# mems.net
KiCad netlist of a schematic drawn in Altium Designer
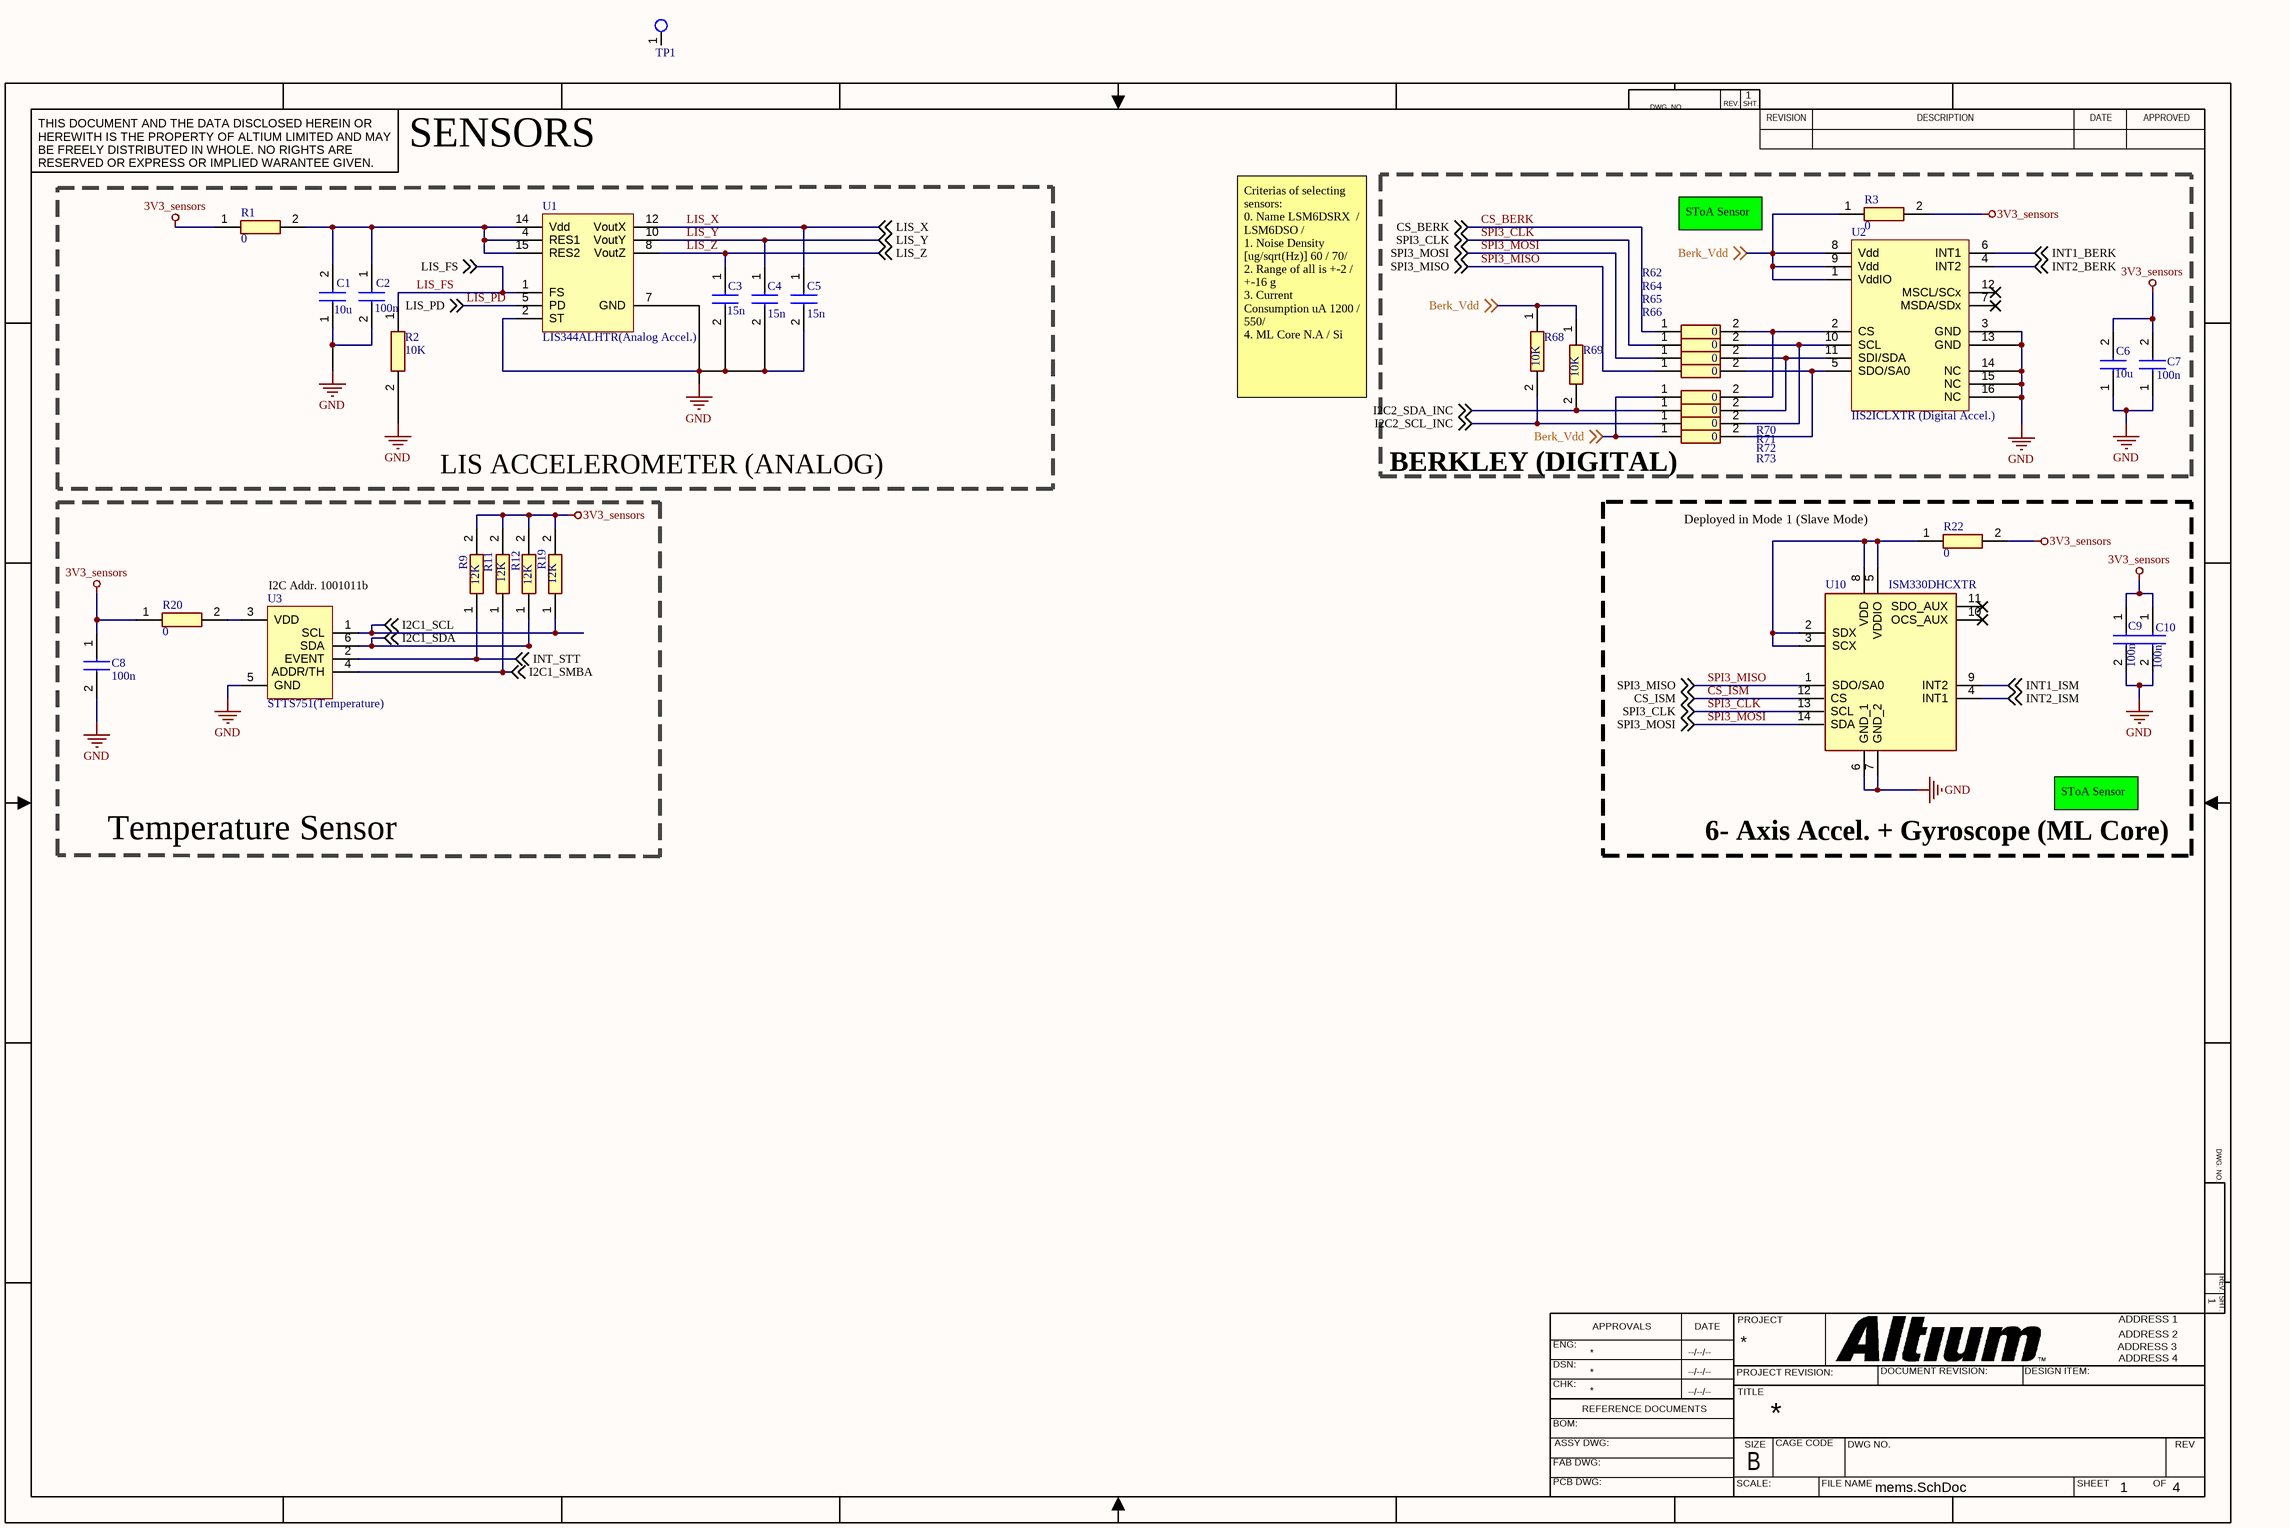
[diagram p0: mems.SchDoc]

(export (version "E")
  (design (tool "Eeschema 10.0.6"))
  (components
    (comp (ref "C1")
      (value "10u")
      (footprint "SamacSys:CAPC1608X100N")
      (description "Capacitor")
      (fields
        (field (name "MOUSER2 PART NUMBER") "963-LMK107BBJ106KALT")
        (field (name "MANUFACTURER_PART_NUMBER") "LMK107BBJ106KALT")
      )
      (libsource (lib "*") (part "LMK107BBJ106KALT"))
    )
    (comp (ref "C2")
      (value "100n")
      (footprint "SamacSys:CAPC1608X87N")
      (description "Capacitor")
      (fields (field (name "MANUFACTURER_PART_NUMBER") "885012206071"))
      (libsource (lib "*") (part "885012206071"))
    )
    (comp (ref "C3")
      (value "15n")
      (footprint "SamacSys:CAPC1608X87N")
      (description "Capacitor")
      (fields (field (name "MANUFACTURER_PART_NUMBER") "885012206041"))
      (libsource (lib "*") (part "885012206041"))
    )
    (comp (ref "C4")
      (value "15n")
      (footprint "SamacSys:CAPC1608X87N")
      (description "Capacitor")
      (fields (field (name "MANUFACTURER_PART_NUMBER") "885012206041"))
      (libsource (lib "*") (part "885012206041"))
    )
    (comp (ref "C5")
      (value "15n")
      (footprint "SamacSys:CAPC1608X87N")
      (description "Capacitor")
      (fields (field (name "MANUFACTURER_PART_NUMBER") "885012206041"))
      (libsource (lib "*") (part "885012206041"))
    )
    (comp (ref "C6")
      (value "10u")
      (footprint "SamacSys:CAPC1608X100N")
      (description "Capacitor")
      (fields
        (field (name "MOUSER2 PART NUMBER") "963-LMK107BBJ106KALT")
        (field (name "MANUFACTURER_PART_NUMBER") "LMK107BBJ106KALT")
      )
      (libsource (lib "*") (part "LMK107BBJ106KALT"))
    )
    (comp (ref "C7")
      (value "100n")
      (footprint "SamacSys:CAPC1608X87N")
      (description "Capacitor")
      (fields (field (name "MANUFACTURER_PART_NUMBER") "885012206071"))
      (libsource (lib "*") (part "885012206071"))
    )
    (comp (ref "C8")
      (value "100n")
      (footprint "SamacSys:CAPC1608X87N")
      (description "Capacitor")
      (fields (field (name "MANUFACTURER_PART_NUMBER") "885012206071"))
      (libsource (lib "*") (part "885012206071"))
    )
    (comp (ref "C9")
      (value "100n")
      (footprint "SamacSys:CAPC1608X87N")
      (description "Capacitor")
      (fields (field (name "MANUFACTURER_PART_NUMBER") "885012206071"))
      (libsource (lib "*") (part "885012206071"))
    )
    (comp (ref "C10")
      (value "100n")
      (footprint "SamacSys:CAPC1608X87N")
      (description "Capacitor")
      (fields (field (name "MANUFACTURER_PART_NUMBER") "885012206071"))
      (libsource (lib "*") (part "885012206071"))
    )
    (comp (ref "R1")
      (value "0")
      (footprint "SamacSys:RESC1608X55N")
      (description "Resistor")
      (fields (field (name "MANUFACTURER_PART_NUMBER") "RC0603FR-070RL"))
      (libsource (lib "*") (part "RC0603FR-070RL"))
    )
    (comp (ref "R2")
      (value "10K")
      (footprint "SamacSys:ERJ3EK_(0603)")
      (description "Resistor")
      (fields
        (field (name "MOUSER2 PART NUMBER") "667-ERJ-3EKF1002V")
        (field (name "MANUFACTURER_PART_NUMBER") "ERJ-3EKF1002V")
      )
      (libsource (lib "*") (part "ERJ-3EKF1002V"))
    )
    (comp (ref "R3")
      (value "0")
      (footprint "SamacSys:RESC1608X55N")
      (description "Resistor")
      (fields (field (name "MANUFACTURER_PART_NUMBER") "RC0603FR-070RL"))
      (libsource (lib "*") (part "RC0603FR-070RL"))
    )
    (comp (ref "R9")
      (value "12K")
      (footprint "SamacSys:RESC0603X26N")
      (description "Resistor")
      (fields (field (name "MANUFACTURER_PART_NUMBER") "ERJ-1RHD1202C"))
      (libsource (lib "*") (part "ERJ-1RHD1202C"))
    )
    (comp (ref "R11")
      (value "12K")
      (footprint "SamacSys:RESC0603X26N")
      (description "Resistor")
      (fields (field (name "MANUFACTURER_PART_NUMBER") "ERJ-1RHD1202C"))
      (libsource (lib "*") (part "ERJ-1RHD1202C"))
    )
    (comp (ref "R12")
      (value "12K")
      (footprint "SamacSys:RESC0603X26N")
      (description "Resistor")
      (fields (field (name "MANUFACTURER_PART_NUMBER") "ERJ-1RHD1202C"))
      (libsource (lib "*") (part "ERJ-1RHD1202C"))
    )
    (comp (ref "R19")
      (value "12K")
      (footprint "RESC0603X26N")
      (description "Resistor")
      (fields (field (name "MANUFACTURER_PART_NUMBER") "ERJ-1RHD1202C"))
      (libsource (lib "*") (part "ERJ-1RHD1202C"))
    )
    (comp (ref "R20")
      (value "0")
      (footprint "SamacSys:RESC1608X55N")
      (description "Resistor")
      (fields (field (name "MANUFACTURER_PART_NUMBER") "RC0603FR-070RL"))
      (libsource (lib "*") (part "RC0603FR-070RL"))
    )
    (comp (ref "R22")
      (value "0")
      (footprint "SamacSys:RESC1608X55N")
      (description "Resistor")
      (fields (field (name "MANUFACTURER_PART_NUMBER") "RC0603FR-070RL"))
      (libsource (lib "*") (part "RC0603FR-070RL"))
    )
    (comp (ref "R62")
      (value "0")
      (footprint "RESC1608X55N")
      (description "Resistor")
      (fields (field (name "MANUFACTURER_PART_NUMBER") "RC0603FR-070RL"))
      (libsource (lib "*") (part "RC0603FR-070RL"))
    )
    (comp (ref "R64")
      (value "0")
      (footprint "RESC1608X55N")
      (description "Resistor")
      (fields (field (name "MANUFACTURER_PART_NUMBER") "RC0603FR-070RL"))
      (libsource (lib "*") (part "RC0603FR-070RL"))
    )
    (comp (ref "R65")
      (value "0")
      (footprint "RESC1608X55N")
      (description "Resistor")
      (fields (field (name "MANUFACTURER_PART_NUMBER") "RC0603FR-070RL"))
      (libsource (lib "*") (part "RC0603FR-070RL"))
    )
    (comp (ref "R66")
      (value "0")
      (footprint "RESC1608X55N")
      (description "Resistor")
      (fields (field (name "MANUFACTURER_PART_NUMBER") "RC0603FR-070RL"))
      (libsource (lib "*") (part "RC0603FR-070RL"))
    )
    (comp (ref "R68")
      (value "10K")
      (footprint "ERJ3EK_(0603)")
      (description "Resistor")
      (fields
        (field (name "MOUSER2 PART NUMBER") "667-ERJ-3EKF1002V")
        (field (name "MANUFACTURER_PART_NUMBER") "ERJ-3EKF1002V")
      )
      (libsource (lib "*") (part "ERJ-3EKF1002V"))
    )
    (comp (ref "R69")
      (value "10K")
      (footprint "ERJ3EK_(0603)")
      (description "Resistor")
      (fields
        (field (name "MOUSER2 PART NUMBER") "667-ERJ-3EKF1002V")
        (field (name "MANUFACTURER_PART_NUMBER") "ERJ-3EKF1002V")
      )
      (libsource (lib "*") (part "ERJ-3EKF1002V"))
    )
    (comp (ref "R70")
      (value "0")
      (footprint "RESC1608X55N")
      (description "Resistor")
      (fields (field (name "MANUFACTURER_PART_NUMBER") "RC0603FR-070RL"))
      (libsource (lib "*") (part "RC0603FR-070RL"))
    )
    (comp (ref "R71")
      (value "0")
      (footprint "RESC1608X55N")
      (description "Resistor")
      (fields (field (name "MANUFACTURER_PART_NUMBER") "RC0603FR-070RL"))
      (libsource (lib "*") (part "RC0603FR-070RL"))
    )
    (comp (ref "R72")
      (value "0")
      (footprint "RESC1608X55N")
      (description "Resistor")
      (fields (field (name "MANUFACTURER_PART_NUMBER") "RC0603FR-070RL"))
      (libsource (lib "*") (part "RC0603FR-070RL"))
    )
    (comp (ref "R73")
      (value "0")
      (footprint "RESC1608X55N")
      (description "Resistor")
      (fields (field (name "MANUFACTURER_PART_NUMBER") "RC0603FR-070RL"))
      (libsource (lib "*") (part "RC0603FR-070RL"))
    )
    (comp (ref "TP1")
      (value "test_point")
      (footprint "test_point")
      (libsource (lib "shm_schem_lib") (part "test_point"))
    )
    (comp (ref "U1")
      (value "LIS344ALHTR(Analog Accel.)")
      (footprint "LGA16R65P4X4_400X400X160")
      (description "3-axis analog accelerometer, ±2 g / ±6 g user selectable full-scale, ultra compact, low power")
      (fields
        (field (name "MANUFACTURER") "STMicroelectronics")
        (field (name "MANUFACTURER PART NUMBER") "LIS344ALHTR")
      )
      (libsource (lib "shm_schem_lib") (part "LIS344ALHTR"))
    )
    (comp (ref "U2")
      (value "IIS2ICLXTR (Digital Accel.)")
      (footprint "Berkley")
      (description "High-accuracy, high-resolution, low-power, 2- axis digital inclinometer")
      (fields
        (field (name "MANUFACTURER") "STMicroelectronics")
        (field (name "MANUFACTURER PART NUMBER") "IIS2ICLXTR")
      )
      (libsource (lib "shm_schem_lib") (part "IIS2ICLXTR"))
    )
    (comp (ref "U3")
      (value "STTS751(Temperature)")
      (footprint "SOT95P280X145-6N")
      (description "SENSOR TEMPERATURE SMBUS 6UDFN")
      (fields
        (field (name "MANUFACTURER") "STMicroelectronics")
        (field (name "MANUFACTURER PART NUMBER") "STTS751-1DP3F")
      )
      (libsource (lib "shm_schem_lib") (part "STTS751-1DP3F"))
    )
    (comp (ref "U10")
      (value "ISM330DHCXTR")
      (footprint "LGA-14(2.5X3X0.86)")
      (description "iNEMO inertial Sensor include 3D accelerometer & 3D gyroscope; LGA-14L package")
      (fields (field (name "MANUFACTURER") "STMicroelectronics"))
      (libsource (lib "shm_schem_lib") (part "ISM330DHCXTR"))
    )
  )
  (nets
    (net (code "1") (name "3V3_sensors") (class "Default")
      (node (ref "C10") (pin "1") (pinfunction "1_1") (pintype "passive"))
      (node (ref "C6") (pin "2") (pinfunction "2_2") (pintype "passive"))
      (node (ref "C7") (pin "2") (pinfunction "2_2") (pintype "passive"))
      (node (ref "C8") (pin "1") (pinfunction "1_1") (pintype "passive"))
      (node (ref "C9") (pin "1") (pinfunction "1_1") (pintype "passive"))
      (node (ref "R1") (pin "1") (pinfunction "1_1") (pintype "passive"))
      (node (ref "R11") (pin "2") (pinfunction "2_2") (pintype "passive"))
      (node (ref "R12") (pin "2") (pinfunction "2_2") (pintype "passive"))
      (node (ref "R19") (pin "2") (pinfunction "2_2") (pintype "passive"))
      (node (ref "R20") (pin "1") (pinfunction "1_1") (pintype "passive"))
      (node (ref "R22") (pin "2") (pinfunction "2_2") (pintype "passive"))
      (node (ref "R3") (pin "2") (pinfunction "2_2") (pintype "passive"))
      (node (ref "R9") (pin "2") (pinfunction "2_2") (pintype "passive"))
    )
    (net (code "2") (name "Berk_Vdd") (class "Default")
      (node (ref "R3") (pin "1") (pinfunction "1_1") (pintype "passive"))
      (node (ref "R68") (pin "1") (pinfunction "1_1") (pintype "passive"))
      (node (ref "R69") (pin "1") (pinfunction "1_1") (pintype "passive"))
      (node (ref "R70") (pin "1") (pinfunction "1_1") (pintype "passive"))
      (node (ref "R73") (pin "1") (pinfunction "1_1") (pintype "passive"))
      (node (ref "U2") (pin "1") (pinfunction "VddIO_1") (pintype "passive"))
      (node (ref "U2") (pin "8") (pinfunction "Vdd_8") (pintype "passive"))
      (node (ref "U2") (pin "9") (pinfunction "Vdd_9") (pintype "passive"))
    )
    (net (code "3") (name "CS_BERK") (class "Default")
      (node (ref "R62") (pin "1") (pinfunction "1_1") (pintype "passive"))
    )
    (net (code "4") (name "CS_ISM") (class "Default")
      (node (ref "U10") (pin "12") (pinfunction "CS_12") (pintype "passive"))
    )
    (net (code "5") (name "GND") (class "Default")
      (node (ref "C1") (pin "1") (pinfunction "1_1") (pintype "passive"))
      (node (ref "C10") (pin "2") (pinfunction "2_2") (pintype "passive"))
      (node (ref "C2") (pin "2") (pinfunction "2_2") (pintype "passive"))
      (node (ref "C3") (pin "2") (pinfunction "2_2") (pintype "passive"))
      (node (ref "C4") (pin "2") (pinfunction "2_2") (pintype "passive"))
      (node (ref "C5") (pin "2") (pinfunction "2_2") (pintype "passive"))
      (node (ref "C6") (pin "1") (pinfunction "1_1") (pintype "passive"))
      (node (ref "C7") (pin "1") (pinfunction "1_1") (pintype "passive"))
      (node (ref "C8") (pin "2") (pinfunction "2_2") (pintype "passive"))
      (node (ref "C9") (pin "2") (pinfunction "2_2") (pintype "passive"))
      (node (ref "R2") (pin "2") (pinfunction "2_2") (pintype "passive"))
      (node (ref "U1") (pin "2") (pinfunction "ST_2") (pintype "passive"))
      (node (ref "U1") (pin "7") (pinfunction "GND_7") (pintype "passive"))
      (node (ref "U10") (pin "6") (pinfunction "GND_1_6") (pintype "passive"))
      (node (ref "U10") (pin "7") (pinfunction "GND_2_7") (pintype "passive"))
      (node (ref "U2") (pin "13") (pinfunction "GND_13") (pintype "passive"))
      (node (ref "U2") (pin "14") (pinfunction "NC_14") (pintype "passive"))
      (node (ref "U2") (pin "15") (pinfunction "NC_15") (pintype "passive"))
      (node (ref "U2") (pin "16") (pinfunction "NC_16") (pintype "passive"))
      (node (ref "U2") (pin "3") (pinfunction "GND_3") (pintype "passive"))
      (node (ref "U3") (pin "5") (pinfunction "GND_5") (pintype "passive"))
    )
    (net (code "6") (name "I2C1_SCL") (class "Default")
      (node (ref "R19") (pin "1") (pinfunction "1_1") (pintype "passive"))
      (node (ref "U3") (pin "1") (pinfunction "SCL_1") (pintype "passive"))
    )
    (net (code "7") (name "I2C1_SDA") (class "Default")
      (node (ref "R12") (pin "1") (pinfunction "1_1") (pintype "passive"))
      (node (ref "U3") (pin "6") (pinfunction "SDA_6") (pintype "passive"))
    )
    (net (code "8") (name "I2C1_SMBA") (class "Default")
      (node (ref "R11") (pin "1") (pinfunction "1_1") (pintype "passive"))
      (node (ref "U3") (pin "4") (pinfunction "ADDR/TH_4") (pintype "passive"))
    )
    (net (code "9") (name "I2C2_SCL_INC") (class "Default")
      (node (ref "R68") (pin "2") (pinfunction "2_2") (pintype "passive"))
      (node (ref "R72") (pin "1") (pinfunction "1_1") (pintype "passive"))
    )
    (net (code "10") (name "I2C2_SDA_INC") (class "Default")
      (node (ref "R69") (pin "2") (pinfunction "2_2") (pintype "passive"))
      (node (ref "R71") (pin "1") (pinfunction "1_1") (pintype "passive"))
    )
    (net (code "11") (name "INT1_BERK") (class "Default")
      (node (ref "U2") (pin "6") (pinfunction "INT1_6") (pintype "passive"))
    )
    (net (code "12") (name "INT1_ISM") (class "Default")
      (node (ref "U10") (pin "9") (pinfunction "INT2_9") (pintype "passive"))
    )
    (net (code "13") (name "INT2_BERK") (class "Default")
      (node (ref "U2") (pin "4") (pinfunction "INT2_4") (pintype "passive"))
    )
    (net (code "14") (name "INT2_ISM") (class "Default")
      (node (ref "U10") (pin "4") (pinfunction "INT1_4") (pintype "passive"))
    )
    (net (code "15") (name "INT_STT") (class "Default")
      (node (ref "R9") (pin "1") (pinfunction "1_1") (pintype "passive"))
      (node (ref "U3") (pin "2") (pinfunction "EVENT_2") (pintype "passive"))
    )
    (net (code "16") (name "LIS_FS") (class "Default")
      (node (ref "R2") (pin "1") (pinfunction "1_1") (pintype "passive"))
      (node (ref "U1") (pin "1") (pinfunction "FS_1") (pintype "passive"))
    )
    (net (code "17") (name "LIS_PD") (class "Default")
      (node (ref "U1") (pin "5") (pinfunction "PD_5") (pintype "passive"))
    )
    (net (code "18") (name "LIS_X") (class "Default")
      (node (ref "C5") (pin "1") (pinfunction "1_1") (pintype "passive"))
      (node (ref "U1") (pin "12") (pinfunction "VoutX_12") (pintype "passive"))
    )
    (net (code "19") (name "LIS_Y") (class "Default")
      (node (ref "C4") (pin "1") (pinfunction "1_1") (pintype "passive"))
      (node (ref "U1") (pin "10") (pinfunction "VoutY_10") (pintype "passive"))
    )
    (net (code "20") (name "LIS_Z") (class "Default")
      (node (ref "C3") (pin "1") (pinfunction "1_1") (pintype "passive"))
      (node (ref "U1") (pin "8") (pinfunction "VoutZ_8") (pintype "passive"))
    )
    (net (code "21") (name "Net-(U1-RES1)") (class "Default")
      (node (ref "C1") (pin "2") (pinfunction "2_2") (pintype "passive"))
      (node (ref "C2") (pin "1") (pinfunction "1_1") (pintype "passive"))
      (node (ref "R1") (pin "2") (pinfunction "2_2") (pintype "passive"))
      (node (ref "U1") (pin "14") (pinfunction "Vdd_14") (pintype "passive"))
      (node (ref "U1") (pin "15") (pinfunction "RES2_15") (pintype "passive"))
      (node (ref "U1") (pin "4") (pinfunction "RES1_4") (pintype "passive"))
    )
    (net (code "22") (name "Net-(U2-CS)") (class "Default")
      (node (ref "R62") (pin "2") (pinfunction "2_2") (pintype "passive"))
      (node (ref "R70") (pin "2") (pinfunction "2_2") (pintype "passive"))
      (node (ref "U2") (pin "2") (pinfunction "CS_2") (pintype "passive"))
    )
    (net (code "23") (name "Net-(U2-SCL)") (class "Default")
      (node (ref "R64") (pin "2") (pinfunction "2_2") (pintype "passive"))
      (node (ref "R72") (pin "2") (pinfunction "2_2") (pintype "passive"))
      (node (ref "U2") (pin "10") (pinfunction "SCL_10") (pintype "passive"))
    )
    (net (code "24") (name "Net-(U2-SDI{slash}SDA)") (class "Default")
      (node (ref "R65") (pin "2") (pinfunction "2_2") (pintype "passive"))
      (node (ref "R71") (pin "2") (pinfunction "2_2") (pintype "passive"))
      (node (ref "U2") (pin "11") (pinfunction "SDI/SDA_11") (pintype "passive"))
    )
    (net (code "25") (name "Net-(U2-SDO{slash}SA0)") (class "Default")
      (node (ref "R66") (pin "2") (pinfunction "2_2") (pintype "passive"))
      (node (ref "R73") (pin "2") (pinfunction "2_2") (pintype "passive"))
      (node (ref "U2") (pin "5") (pinfunction "SDO/SA0_5") (pintype "passive"))
    )
    (net (code "26") (name "Net-(U3-VDD)") (class "Default")
      (node (ref "R20") (pin "2") (pinfunction "2_2") (pintype "passive"))
      (node (ref "U3") (pin "3") (pinfunction "VDD_3") (pintype "passive"))
    )
    (net (code "27") (name "Net-(U10-SCX)") (class "Default")
      (node (ref "R22") (pin "1") (pinfunction "1_1") (pintype "passive"))
      (node (ref "U10") (pin "2") (pinfunction "SDX_2") (pintype "passive"))
      (node (ref "U10") (pin "3") (pinfunction "SCX_3") (pintype "passive"))
      (node (ref "U10") (pin "5") (pinfunction "VDDIO_5") (pintype "passive"))
      (node (ref "U10") (pin "8") (pinfunction "VDD_8") (pintype "passive"))
    )
    (net (code "28") (name "SPI3_CLK") (class "Default")
      (node (ref "R64") (pin "1") (pinfunction "1_1") (pintype "passive"))
      (node (ref "U10") (pin "13") (pinfunction "SCL_13") (pintype "passive"))
    )
    (net (code "29") (name "SPI3_MISO") (class "Default")
      (node (ref "R66") (pin "1") (pinfunction "1_1") (pintype "passive"))
      (node (ref "U10") (pin "1") (pinfunction "SDO/SA0_1") (pintype "passive"))
    )
    (net (code "30") (name "SPI3_MOSI") (class "Default")
      (node (ref "R65") (pin "1") (pinfunction "1_1") (pintype "passive"))
      (node (ref "U10") (pin "14") (pinfunction "SDA_14") (pintype "passive"))
    )
    (net (code "31") (name "unconnected-(TP1-TP-Pad1)") (class "Default")
      (node (ref "TP1") (pin "1") (pinfunction "TP_1") (pintype "passive"))
    )
    (net (code "32") (name "unconnected-(U2-MSCL{slash}SCx-Pad12)") (class "Default")
      (node (ref "U2") (pin "12") (pinfunction "MSCL/SCx_12") (pintype "passive+no_connect"))
    )
    (net (code "33") (name "unconnected-(U2-MSDA{slash}SDx-Pad7)") (class "Default")
      (node (ref "U2") (pin "7") (pinfunction "MSDA/SDx_7") (pintype "passive+no_connect"))
    )
    (net (code "34") (name "unconnected-(U10-OCS_AUX-Pad10)") (class "Default")
      (node (ref "U10") (pin "10") (pinfunction "OCS_AUX_10") (pintype "passive+no_connect"))
    )
    (net (code "35") (name "unconnected-(U10-SDO_AUX-Pad11)") (class "Default")
      (node (ref "U10") (pin "11") (pinfunction "SDO_AUX_11") (pintype "passive+no_connect"))
    )
  )
)
